# projet_pcb_F103.net
KiCad netlist of a schematic drawn in Altium Designer
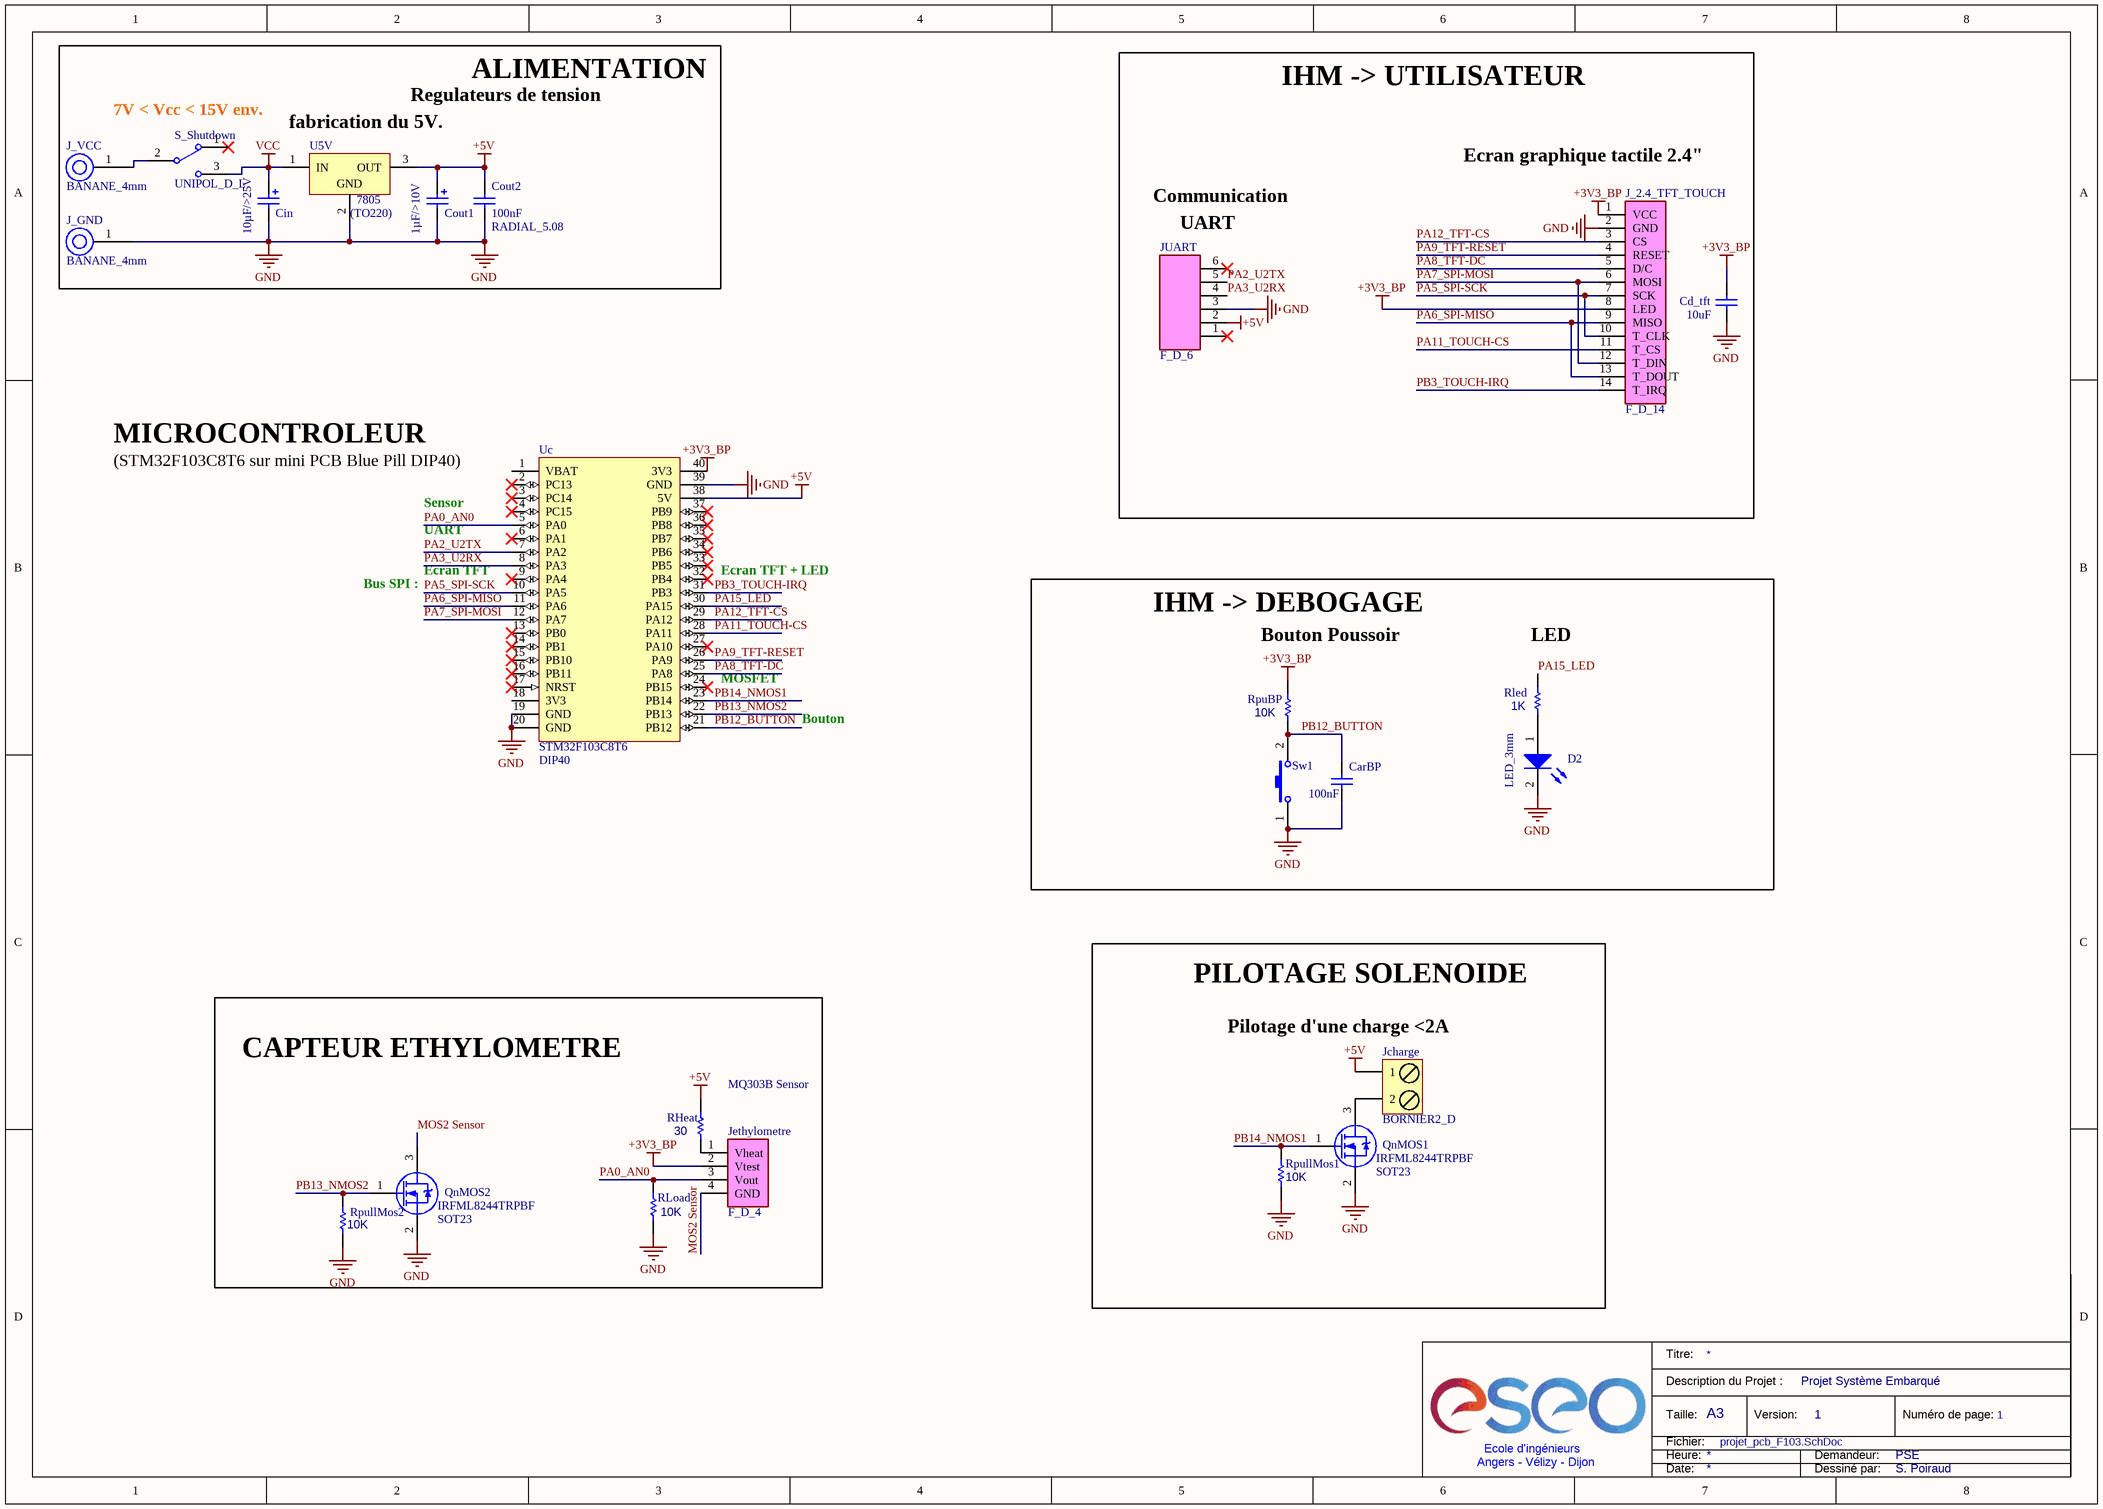
[diagram p0: projet_pcb_F103.SchDoc]

(export (version "E")
  (design (tool "Eeschema 10.0.6"))
  (components
    (comp (ref "CarBP")
      (value "100nF")
      (footprint "CONDENSATEUR_CERAMIQUE_RADIAL_5.08")
      (description "CONDENSATEUR TRAVERSANT CERAMIQUE RADIAL 5.08mm")
      (fields (field (name "Comment") "CONDENSATEUR_CER_RAD_5.08"))
      (libsource (lib "composants passifs") (part "CONDENSATEUR_CER_RAD_5.08"))
    )
    (comp (ref "Cd_tft")
      (value "10uF")
      (footprint "CONDENSATEUR_POLARISE_ELECTROLYTIQUE_RADIAL_2.54/5.08")
      (description "Capacitor")
      (fields (field (name "PUBLISHER") "Altium Limited"))
      (libsource (lib "_ROBOT") (part "Condensateur"))
    )
    (comp (ref "Cin")
      (value "10µF/>25V")
      (footprint "CONDENSATEUR_POLARISE_ELECTROLYTIQUE_RADIAL_2.0/5.08")
      (description "CONDENSATEUR POLARISE ELECTROLYTIQUE RADIAL 2.0/5.08")
      (fields (field (name "Comment") "CONDENSATEUR_POL_ELECTROLY_RAD_2.0/5.08"))
      (libsource (lib "composants passifs") (part "CONDENSATEUR_POL_ELECTROLY_RAD_2.0/5.08"))
    )
    (comp (ref "Cout1")
      (value "1µF/>10V")
      (footprint "CONDENSATEUR_POLARISE_ELECTROLYTIQUE_RADIAL_2.0/5.08")
      (description "CONDENSATEUR POLARISE ELECTROLYTIQUE RADIAL 2.0/5.08")
      (fields (field (name "Comment") "CONDENSATEUR_POL_ELECTROLY_RAD_2.0/5.08"))
      (libsource (lib "composants passifs") (part "CONDENSATEUR_POL_ELECTROLY_RAD_2.0/5.08"))
    )
    (comp (ref "Cout2")
      (value "100nF")
      (footprint "CONDENSATEUR_CERAMIQUE_RADIAL_5.08")
      (description "CONDENSATEUR TRAVERSANT CERAMIQUE RADIAL 5.08mm")
      (fields (field (name "TYPE") "RADIAL_5.08") (field (name "Comment") "CONDENSATEUR_CER_RAD_5.08"))
      (libsource (lib "composants passifs") (part "CONDENSATEUR_CER_RAD_5.08"))
    )
    (comp (ref "D2")
      (value "LED_3MM")
      (footprint "LED_3MM")
      (description "LED 3MM - ROUGE/VERTE/JAUNE")
      (fields (field (name "TYPE") "LED_3mm"))
      (libsource (lib "affichage") (part "LED_3MM"))
    )
    (comp (ref "Jcharge")
      (value "BORNIER2 DROIT A VIS")
      (footprint "BORNIER2_A_VIS")
      (description "BORNIER 2 PLOTS DROIT A VIS 5.08mm")
      (fields (field (name "TYPE") "BORNIER2_D"))
      (libsource (lib "connecteurs") (part "BORNIER2_DROIT_A VIS"))
    )
    (comp (ref "Jethylometre")
      (value "BARRETTE_4 CONTACTS_1 RANGEE_FEMELLE_DROITE")
      (footprint "BARRETTE_4_F_D")
      (description "BARRETTE 4 CONTACTS 1 RANGEE FEMELLE DROITE")
      (fields (field (name "TYPE") "F_D_4"))
      (libsource (lib "connecteurs") (part "BARRETTE_4 CONTACTS_1 RANGEE_FEMELLE_DROITE"))
    )
    (comp (ref "JUART")
      (value "BARRETTE_6 CONTACTS_1 RANGEE_FEMELLE_DROITE")
      (footprint "BARRETTE_6_F_D")
      (description "BARRETTE 6 CONTACTS 1 RANGEE FEMELLE DROITE")
      (fields (field (name "TYPE") "F_D_6"))
      (libsource (lib "connecteurs") (part "BARRETTE_6 CONTACTS_1 RANGEE_FEMELLE_DROITE"))
    )
    (comp (ref "J_2.4_TFT_TOUCH")
      (value "BARRETTE_14 CONTACTS_1 RANGEE_FEMELLE_DROITE")
      (footprint "BARRETTE_14_F_D")
      (fields (field (name "TYPE") "F_D_14"))
      (libsource (lib "connecteurs") (part "BARRETTE_14 CONTACTS_1 RANGEE_FEMELLE_DROITE"))
    )
    (comp (ref "J_GND")
      (value "DOUILLE BANANE 4mm")
      (footprint "DOUILLE_BANANE_4mm")
      (description "DOUILLE BANANE 4 mm")
      (fields (field (name "TYPE") "BANANE_4mm"))
      (libsource (lib "connecteurs") (part "DOUILLE_BANANE_4mm"))
    )
    (comp (ref "J_VCC")
      (value "DOUILLE BANANE 4mm")
      (footprint "DOUILLE_BANANE_4mm")
      (description "DOUILLE BANANE 4 mm")
      (fields (field (name "TYPE") "BANANE_4mm"))
      (libsource (lib "connecteurs") (part "DOUILLE_BANANE_4mm"))
    )
    (comp (ref "QnMOS1")
      (value "TRANSISTOR_MOSFET-N_SOT23_GSD")
      (footprint "TRANSISTOR_MOSFET-N_SOT23_GSD")
      (description "TRANSISTOR MOSFET CANAL N BOITIER SOT23_GSD")
      (fields (field (name "TYPE") "IRFML8244TRPBF") (field (name "PACKAGE") "SOT23"))
      (libsource (lib "composants actifs") (part "TRANSISTOR_MOSFET-N_SOT23_GSD"))
    )
    (comp (ref "QnMOS2")
      (value "TRANSISTOR_MOSFET-N_SOT23_GSD")
      (footprint "TRANSISTOR_MOSFET-N_SOT23_GSD")
      (description "TRANSISTOR MOSFET CANAL N BOITIER SOT23_GSD")
      (fields (field (name "TYPE") "IRFML8244TRPBF") (field (name "PACKAGE") "SOT23"))
      (libsource (lib "composants actifs") (part "TRANSISTOR_MOSFET-N_SOT23_GSD"))
    )
    (comp (ref "RHeat")
      (value "30")
      (footprint "RESISTANCE_1/4W")
      (description "RESISTANCE TRAVERSANTE AXIALE 1/4W")
      (fields (field (name "Comment") "RESISTANCE_AXIALE_1/4W"))
      (libsource (lib "composants passifs") (part "RESISTANCE_AXIALE_1/4W"))
    )
    (comp (ref "Rled")
      (value "1K")
      (footprint "RESISTANCE_1/4W")
      (description "RESISTANCE TRAVERSANTE AXIALE 1/4W")
      (fields (field (name "Comment") "RESISTANCE_AXIALE_1/4W"))
      (libsource (lib "composants passifs") (part "RESISTANCE_AXIALE_1/4W"))
    )
    (comp (ref "RLoad")
      (value "10K")
      (footprint "RESISTANCE_1/4W")
      (description "RESISTANCE TRAVERSANTE AXIALE 1/4W")
      (fields (field (name "Comment") "RESISTANCE_AXIALE_1/4W"))
      (libsource (lib "composants passifs") (part "RESISTANCE_AXIALE_1/4W"))
    )
    (comp (ref "RpuBP")
      (value "10K")
      (footprint "RESISTANCE_1/4W")
      (description "RESISTANCE TRAVERSANTE AXIALE 1/4W")
      (fields (field (name "Comment") "RESISTANCE_AXIALE_1/4W"))
      (libsource (lib "composants passifs") (part "RESISTANCE_AXIALE_1/4W"))
    )
    (comp (ref "RpullMos1")
      (value "10K")
      (footprint "RESISTANCE_1/4W")
      (description "RESISTANCE TRAVERSANTE AXIALE 1/4W")
      (fields (field (name "Comment") "RESISTANCE_AXIALE_1/4W"))
      (libsource (lib "composants passifs") (part "RESISTANCE_AXIALE_1/4W"))
    )
    (comp (ref "RpullMos2")
      (value "10K")
      (footprint "RESISTANCE_1/4W")
      (description "RESISTANCE TRAVERSANTE AXIALE 1/4W")
      (fields (field (name "Comment") "RESISTANCE_AXIALE_1/4W"))
      (libsource (lib "composants passifs") (part "RESISTANCE_AXIALE_1/4W"))
    )
    (comp (ref "Sw1")
      (value "BOUTON_POUSSOIR_MINIATURE_TRAVERSANT")
      (footprint "BOUTON_POUSSE_PLAT_6x6")
      (description "BOUTON POUSSOIR MINIATURE TRAVERSANT ON/OFF")
      (libsource (lib "commutation") (part "BOUTON_POUSSOIR_MINIATURE_TRAVERSANT"))
    )
    (comp (ref "S_Shutdown")
      (value "INTERRUPTEUR_UNIPOLAIRE_DROIT_A_LEVIER")
      (footprint "INTER_UNIPOL_DROIT_LEVIER")
      (fields (field (name "TYPE") "UNIPOL_D_L"))
      (libsource (lib "commutation") (part "INTERRUPTEUR_UNIPOLAIRE_DROIT_A_LEVIER"))
    )
    (comp (ref "U5V")
      (value "REGULATEUR_TO220_78XX")
      (footprint "REGULATEUR_TO220_78XX")
      (description "REGULATEUR DE TENSION POSITIVE 78XX BOITIER TO220")
      (fields (field (name "TYPE") "7805") (field (name "PACKAGE") "(TO220)"))
      (libsource (lib "composants actifs") (part "REGULATEUR_TO220_78XX"))
    )
    (comp (ref "Uc")
      (value "STM32F103C8T6/PCB_DIP40")
      (footprint "STM32F103C8T6_DIP40")
      (fields (field (name "TYPE") "STM32F103C8T6") (field (name "PACKAGE") "DIP40"))
      (libsource (lib "circuits integres") (part "STM32F103C8T6/PCB_DIP40"))
    )
  )
  (nets
    (net (code "1") (name "+3V3_BP") (class "Default")
      (node (ref "Cd_tft") (pin "1") (pinfunction "1_1") (pintype "passive"))
      (node (ref "J_2.4_TFT_TOUCH") (pin "1") (pinfunction "VCC_1") (pintype "passive"))
      (node (ref "J_2.4_TFT_TOUCH") (pin "8") (pinfunction "LED_8") (pintype "passive"))
      (node (ref "Jethylometre") (pin "2") (pinfunction "Vtest_2") (pintype "passive"))
      (node (ref "RpuBP") (pin "1") (pinfunction "1_1") (pintype "passive"))
      (node (ref "Uc") (pin "40") (pinfunction "3V3_40") (pintype "power_in"))
    )
    (net (code "2") (name "+5V") (class "Default")
      (node (ref "Cout1") (pin "1") (pinfunction "1_1") (pintype "passive"))
      (node (ref "Cout2") (pin "2") (pinfunction "2_2") (pintype "passive"))
      (node (ref "JUART") (pin "2") (pinfunction "2_2") (pintype "passive"))
      (node (ref "Jcharge") (pin "1") (pinfunction "1_1") (pintype "passive"))
      (node (ref "RHeat") (pin "1") (pinfunction "1_1") (pintype "passive"))
      (node (ref "U5V") (pin "3") (pinfunction "OUT_3") (pintype "power_in"))
      (node (ref "Uc") (pin "38") (pinfunction "5V_38") (pintype "power_in"))
    )
    (net (code "4") (name "/MOS2 Sensor") (class "Default")
      (node (ref "Jethylometre") (pin "4") (pinfunction "GND_4") (pintype "passive"))
      (node (ref "QnMOS2") (pin "3") (pinfunction "D_3") (pintype "passive"))
    )
    (net (code "5") (name "/PA0_AN0") (class "Default")
      (node (ref "Jethylometre") (pin "3") (pinfunction "Vout_3") (pintype "passive"))
      (node (ref "RLoad") (pin "2") (pinfunction "2_2") (pintype "passive"))
      (node (ref "Uc") (pin "5") (pinfunction "PA0_5") (pintype "bidirectional"))
    )
    (net (code "6") (name "/PA2_U2TX") (class "Default")
      (node (ref "JUART") (pin "5") (pinfunction "5_5") (pintype "passive"))
      (node (ref "Uc") (pin "7") (pinfunction "PA2_7") (pintype "bidirectional"))
    )
    (net (code "7") (name "/PA3_U2RX") (class "Default")
      (node (ref "JUART") (pin "4") (pinfunction "4_4") (pintype "passive"))
      (node (ref "Uc") (pin "8") (pinfunction "PA3_8") (pintype "bidirectional"))
    )
    (net (code "8") (name "/PA5_SPI-SCK") (class "Default")
      (node (ref "J_2.4_TFT_TOUCH") (pin "10") (pinfunction "T_CLK_10") (pintype "passive"))
      (node (ref "J_2.4_TFT_TOUCH") (pin "7") (pinfunction "SCK_7") (pintype "passive"))
      (node (ref "Uc") (pin "10") (pinfunction "PA5_10") (pintype "bidirectional"))
    )
    (net (code "9") (name "/PA6_SPI-MISO") (class "Default")
      (node (ref "J_2.4_TFT_TOUCH") (pin "13") (pinfunction "T_DOUT_13") (pintype "passive"))
      (node (ref "J_2.4_TFT_TOUCH") (pin "9") (pinfunction "MISO_9") (pintype "passive"))
      (node (ref "Uc") (pin "11") (pinfunction "PA6_11") (pintype "bidirectional"))
    )
    (net (code "10") (name "/PA7_SPI-MOSI") (class "Default")
      (node (ref "J_2.4_TFT_TOUCH") (pin "12") (pinfunction "T_DIN_12") (pintype "passive"))
      (node (ref "J_2.4_TFT_TOUCH") (pin "6") (pinfunction "MOSI_6") (pintype "passive"))
      (node (ref "Uc") (pin "12") (pinfunction "PA7_12") (pintype "bidirectional"))
    )
    (net (code "11") (name "/PA8_TFT-DC") (class "Default")
      (node (ref "J_2.4_TFT_TOUCH") (pin "5") (pinfunction "D/C_5") (pintype "passive"))
      (node (ref "Uc") (pin "25") (pinfunction "PA8_25") (pintype "bidirectional"))
    )
    (net (code "12") (name "/PA9_TFT-RESET") (class "Default")
      (node (ref "J_2.4_TFT_TOUCH") (pin "4") (pinfunction "RESET_4") (pintype "passive"))
      (node (ref "Uc") (pin "26") (pinfunction "PA9_26") (pintype "bidirectional"))
    )
    (net (code "13") (name "/PA11_TOUCH-CS") (class "Default")
      (node (ref "J_2.4_TFT_TOUCH") (pin "11") (pinfunction "T_CS_11") (pintype "passive"))
      (node (ref "Uc") (pin "28") (pinfunction "PA11_28") (pintype "bidirectional"))
    )
    (net (code "14") (name "/PA12_TFT-CS") (class "Default")
      (node (ref "J_2.4_TFT_TOUCH") (pin "3") (pinfunction "CS_3") (pintype "passive"))
      (node (ref "Uc") (pin "29") (pinfunction "PA12_29") (pintype "bidirectional"))
    )
    (net (code "15") (name "/PA15_LED") (class "Default")
      (node (ref "Rled") (pin "1") (pinfunction "1_1") (pintype "passive"))
      (node (ref "Uc") (pin "30") (pinfunction "PA15_30") (pintype "bidirectional"))
    )
    (net (code "16") (name "/PB3_TOUCH-IRQ") (class "Default")
      (node (ref "J_2.4_TFT_TOUCH") (pin "14") (pinfunction "T_IRQ_14") (pintype "passive"))
      (node (ref "Uc") (pin "31") (pinfunction "PB3_31") (pintype "bidirectional"))
    )
    (net (code "17") (name "/PB12_BUTTON") (class "Default")
      (node (ref "CarBP") (pin "2") (pinfunction "2_2") (pintype "passive"))
      (node (ref "RpuBP") (pin "2") (pinfunction "2_2") (pintype "passive"))
      (node (ref "Sw1") (pin "2") (pinfunction "2_2") (pintype "passive"))
      (node (ref "Uc") (pin "21") (pinfunction "PB12_21") (pintype "bidirectional"))
    )
    (net (code "18") (name "/PB13_NMOS2") (class "Default")
      (node (ref "QnMOS2") (pin "1") (pinfunction "G_1") (pintype "passive"))
      (node (ref "RpullMos2") (pin "2") (pinfunction "2_2") (pintype "passive"))
      (node (ref "Uc") (pin "22") (pinfunction "PB13_22") (pintype "bidirectional"))
    )
    (net (code "19") (name "/PB14_NMOS1") (class "Default")
      (node (ref "QnMOS1") (pin "1") (pinfunction "G_1") (pintype "passive"))
      (node (ref "RpullMos1") (pin "2") (pinfunction "2_2") (pintype "passive"))
      (node (ref "Uc") (pin "23") (pinfunction "PB14_23") (pintype "bidirectional"))
    )
    (net (code "20") (name "GND") (class "Default")
      (node (ref "CarBP") (pin "1") (pinfunction "1_1") (pintype "passive"))
      (node (ref "Cd_tft") (pin "2") (pinfunction "2_2") (pintype "passive"))
      (node (ref "Cin") (pin "2") (pinfunction "2_2") (pintype "passive"))
      (node (ref "Cout1") (pin "2") (pinfunction "2_2") (pintype "passive"))
      (node (ref "Cout2") (pin "1") (pinfunction "1_1") (pintype "passive"))
      (node (ref "D2") (pin "2") (pinfunction "2_2") (pintype "passive"))
      (node (ref "JUART") (pin "3") (pinfunction "3_3") (pintype "passive"))
      (node (ref "J_2.4_TFT_TOUCH") (pin "2") (pinfunction "GND_2") (pintype "passive"))
      (node (ref "J_GND") (pin "1") (pinfunction "1_1") (pintype "passive"))
      (node (ref "QnMOS1") (pin "2") (pinfunction "S_2") (pintype "passive"))
      (node (ref "QnMOS2") (pin "2") (pinfunction "S_2") (pintype "passive"))
      (node (ref "RLoad") (pin "1") (pinfunction "1_1") (pintype "passive"))
      (node (ref "RpullMos1") (pin "1") (pinfunction "1_1") (pintype "passive"))
      (node (ref "RpullMos2") (pin "1") (pinfunction "1_1") (pintype "passive"))
      (node (ref "Sw1") (pin "1") (pinfunction "1_1") (pintype "passive"))
      (node (ref "U5V") (pin "2") (pinfunction "GND_2") (pintype "power_in"))
      (node (ref "Uc") (pin "19") (pinfunction "GND_19") (pintype "power_in"))
      (node (ref "Uc") (pin "20") (pinfunction "GND_20") (pintype "power_in"))
      (node (ref "Uc") (pin "39") (pinfunction "GND_39") (pintype "power_in"))
    )
    (net (code "21") (name "Net-(D2-Pad1)") (class "Default")
      (node (ref "D2") (pin "1") (pinfunction "1_1") (pintype "passive"))
      (node (ref "Rled") (pin "2") (pinfunction "2_2") (pintype "passive"))
    )
    (net (code "22") (name "Net-(J_VCC-Pad1)") (class "Default")
      (node (ref "J_VCC") (pin "1") (pinfunction "1_1") (pintype "passive"))
      (node (ref "S_Shutdown") (pin "2") (pinfunction "2_2") (pintype "passive"))
    )
    (net (code "23") (name "Net-(Jethylometre-Vheat)") (class "Default")
      (node (ref "Jethylometre") (pin "1") (pinfunction "Vheat_1") (pintype "passive"))
      (node (ref "RHeat") (pin "2") (pinfunction "2_2") (pintype "passive"))
    )
    (net (code "24") (name "Net-(QnMOS1-D)") (class "Default")
      (node (ref "Jcharge") (pin "2") (pinfunction "2_2") (pintype "passive"))
      (node (ref "QnMOS1") (pin "3") (pinfunction "D_3") (pintype "passive"))
    )
    (net (code "25") (name "VCC") (class "Default")
      (node (ref "Cin") (pin "1") (pinfunction "1_1") (pintype "passive"))
      (node (ref "S_Shutdown") (pin "3") (pinfunction "3_3") (pintype "passive"))
      (node (ref "U5V") (pin "1") (pinfunction "IN_1") (pintype "power_in"))
    )
    (net (code "26") (name "unconnected-(JUART-Pad1)") (class "Default")
      (node (ref "JUART") (pin "1") (pinfunction "1_1") (pintype "passive+no_connect"))
    )
    (net (code "27") (name "unconnected-(JUART-Pad6)") (class "Default")
      (node (ref "JUART") (pin "6") (pinfunction "6_6") (pintype "passive+no_connect"))
    )
    (net (code "28") (name "unconnected-(S_Shutdown-Pad1)") (class "Default")
      (node (ref "S_Shutdown") (pin "1") (pinfunction "1_1") (pintype "passive+no_connect"))
    )
    (net (code "29") (name "unconnected-(Uc-3V3-Pad18)") (class "Default")
      (node (ref "Uc") (pin "18") (pinfunction "3V3_18") (pintype "power_in"))
    )
    (net (code "30") (name "unconnected-(Uc-NRST-Pad17)") (class "Default")
      (node (ref "Uc") (pin "17") (pinfunction "NRST_17") (pintype "input+no_connect"))
    )
    (net (code "31") (name "unconnected-(Uc-PA1-Pad6)") (class "Default")
      (node (ref "Uc") (pin "6") (pinfunction "PA1_6") (pintype "bidirectional+no_connect"))
    )
    (net (code "32") (name "unconnected-(Uc-PA4-Pad9)") (class "Default")
      (node (ref "Uc") (pin "9") (pinfunction "PA4_9") (pintype "bidirectional+no_connect"))
    )
    (net (code "33") (name "unconnected-(Uc-PA10-Pad27)") (class "Default")
      (node (ref "Uc") (pin "27") (pinfunction "PA10_27") (pintype "bidirectional+no_connect"))
    )
    (net (code "34") (name "unconnected-(Uc-PB0-Pad13)") (class "Default")
      (node (ref "Uc") (pin "13") (pinfunction "PB0_13") (pintype "bidirectional+no_connect"))
    )
    (net (code "35") (name "unconnected-(Uc-PB1-Pad14)") (class "Default")
      (node (ref "Uc") (pin "14") (pinfunction "PB1_14") (pintype "bidirectional+no_connect"))
    )
    (net (code "36") (name "unconnected-(Uc-PB4-Pad32)") (class "Default")
      (node (ref "Uc") (pin "32") (pinfunction "PB4_32") (pintype "bidirectional+no_connect"))
    )
    (net (code "37") (name "unconnected-(Uc-PB5-Pad33)") (class "Default")
      (node (ref "Uc") (pin "33") (pinfunction "PB5_33") (pintype "bidirectional+no_connect"))
    )
    (net (code "38") (name "unconnected-(Uc-PB6-Pad34)") (class "Default")
      (node (ref "Uc") (pin "34") (pinfunction "PB6_34") (pintype "bidirectional+no_connect"))
    )
    (net (code "39") (name "unconnected-(Uc-PB7-Pad35)") (class "Default")
      (node (ref "Uc") (pin "35") (pinfunction "PB7_35") (pintype "bidirectional+no_connect"))
    )
    (net (code "40") (name "unconnected-(Uc-PB8-Pad36)") (class "Default")
      (node (ref "Uc") (pin "36") (pinfunction "PB8_36") (pintype "bidirectional+no_connect"))
    )
    (net (code "41") (name "unconnected-(Uc-PB9-Pad37)") (class "Default")
      (node (ref "Uc") (pin "37") (pinfunction "PB9_37") (pintype "bidirectional+no_connect"))
    )
    (net (code "42") (name "unconnected-(Uc-PB10-Pad15)") (class "Default")
      (node (ref "Uc") (pin "15") (pinfunction "PB10_15") (pintype "bidirectional+no_connect"))
    )
    (net (code "43") (name "unconnected-(Uc-PB11-Pad16)") (class "Default")
      (node (ref "Uc") (pin "16") (pinfunction "PB11_16") (pintype "bidirectional+no_connect"))
    )
    (net (code "44") (name "unconnected-(Uc-PB15-Pad24)") (class "Default")
      (node (ref "Uc") (pin "24") (pinfunction "PB15_24") (pintype "bidirectional+no_connect"))
    )
    (net (code "45") (name "unconnected-(Uc-PC13-Pad2)") (class "Default")
      (node (ref "Uc") (pin "2") (pinfunction "PC13_2") (pintype "bidirectional+no_connect"))
    )
    (net (code "46") (name "unconnected-(Uc-PC14-Pad3)") (class "Default")
      (node (ref "Uc") (pin "3") (pinfunction "PC14_3") (pintype "bidirectional+no_connect"))
    )
    (net (code "47") (name "unconnected-(Uc-PC15-Pad4)") (class "Default")
      (node (ref "Uc") (pin "4") (pinfunction "PC15_4") (pintype "bidirectional+no_connect"))
    )
    (net (code "48") (name "unconnected-(Uc-VBAT-Pad1)") (class "Default")
      (node (ref "Uc") (pin "1") (pinfunction "VBAT_1") (pintype "power_in"))
    )
  )
)
